# 08-I225-1.net
KiCad netlist of a schematic drawn in Altium Designer
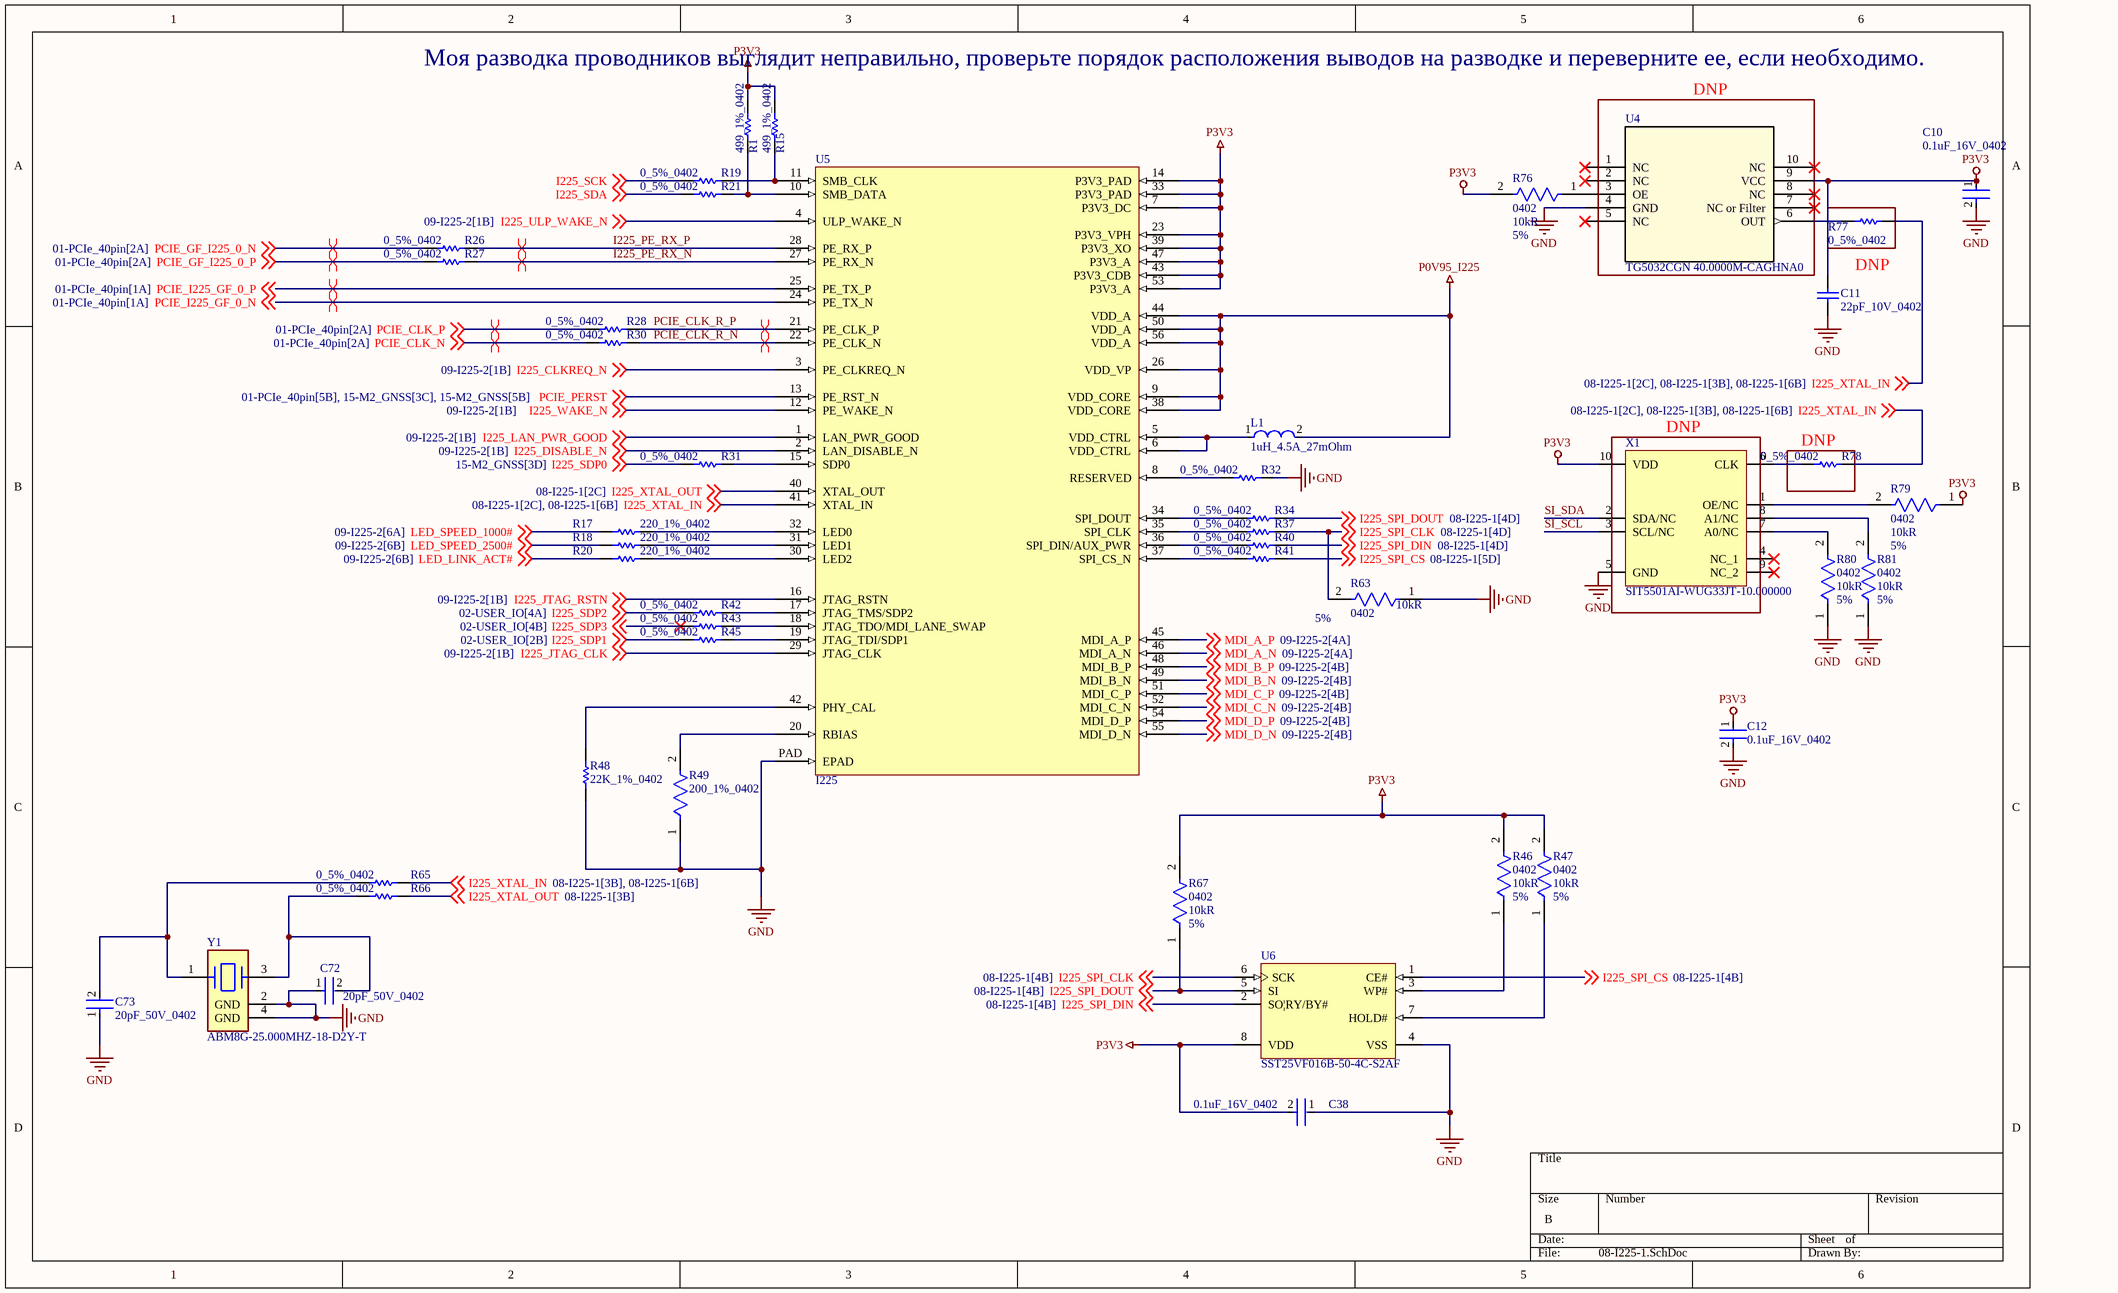
[diagram p0: 08-I225-1.SchDoc]

(export (version "E")
  (design (tool "Eeschema 10.0.6"))
  (components
    (comp (ref "C10")
      (value "0.1uF_16V_0402")
      (footprint "FP-GRM15-MFG")
      (description "CAP CER 0.1UF 16V X7R 0402")
      (fields (field (name "MANUFACTURER PART NUMBER") "GRM155R71C104KA88D") (field (name "TOLERANCE") "10%"))
      (libsource (lib "Altium Content Vault") (part "236180d848d6139a670b325ea6854c9"))
    )
    (comp (ref "C11")
      (value "22pF_10V_0402")
      (footprint "CAPC1005X56X25LL10T15")
      (fields
        (field (name "PART NUMBER") "0402ZA220JAT2A")
        (field (name "MANUFACTURER") "AVX Interconnect / Elco")
      )
      (libsource (lib "Altium Content Vault") (part "CAP"))
    )
    (comp (ref "C12")
      (value "0.1uF_16V_0402")
      (footprint "FP-GRM15-MFG")
      (description "CAP CER 0.1UF 16V X7R 0402")
      (fields (field (name "MANUFACTURER PART NUMBER") "GRM155R71C104KA88D") (field (name "TOLERANCE") "10%"))
      (libsource (lib "Altium Content Vault") (part "236180d848d6139a670b325ea6854c9"))
    )
    (comp (ref "C38")
      (value "0.1uF_16V_0402")
      (footprint "FP-GRM15-MFG")
      (description "CAP CER 0.1UF 16V X7R 0402")
      (fields (field (name "MANUFACTURER PART NUMBER") "GRM155R71C104KA88D") (field (name "TOLERANCE") "10%"))
      (libsource (lib "Altium Content Vault") (part "236180d848d6139a670b325ea6854c9"))
    )
    (comp (ref "C72")
      (value "20pF_50V_0402")
      (footprint "FP-C0402-BB-MFG")
      (description "CAP CER 20PF 50V 5% NP0 0402")
      (fields
        (field (name "MANUFACTURER PART NUMBER") "C0402C200J5GACTU")
        (field (name "OCTOPART") "https://octopart.com/c0402c200j5gactu-kemet-9143900")
      )
      (libsource (lib "Altium Content Vault") (part "b4654b650e69147ec39a6b967a45e02"))
    )
    (comp (ref "C73")
      (value "20pF_50V_0402")
      (footprint "FP-C0402-BB-MFG")
      (description "CAP CER 20PF 50V 5% NP0 0402")
      (fields
        (field (name "MANUFACTURER PART NUMBER") "C0402C200J5GACTU")
        (field (name "OCTOPART") "https://octopart.com/c0402c200j5gactu-kemet-9143900")
      )
      (libsource (lib "Altium Content Vault") (part "b4654b650e69147ec39a6b967a45e02"))
    )
    (comp (ref "L1")
      (value "1uH_4.5A_27mOhm")
      (footprint "FP-IHLP-1616BZ-FP_1_8545x-MFG")
      (description "Fixed Inductors Commercial Low DCR Series SMT 1uH 4.5A 27mΩ 20%")
      (fields (field (name "TOLERANCE") "20%"))
      (libsource (lib "Altium Content Vault") (part "725321dda6339637d4d059423bc1c3c"))
    )
    (comp (ref "R1")
      (value "499_1%_0402")
      (footprint "RESC1005X40X25LL05T05")
      (fields (field (name "MANUFACTURER") "Panasonic") (field (name "PART NUMBER") "ERJ-2RKF4990X"))
      (libsource (lib "Altium Content Vault") (part "RES"))
    )
    (comp (ref "R15")
      (value "499_1%_0402")
      (footprint "RESC1005X40X25LL05T05")
      (fields (field (name "MANUFACTURER") "Panasonic") (field (name "PART NUMBER") "ERJ-2RKF4990X"))
      (libsource (lib "Altium Content Vault") (part "RES"))
    )
    (comp (ref "R17")
      (value "220_1%_0402")
      (footprint "RESC1005X40X25NL10T10")
      (fields (field (name "PART NUMBER") "MC00625W04021220R") (field (name "MANUFACTURER") "Multicomp"))
      (libsource (lib "Altium Content Vault") (part "RES"))
    )
    (comp (ref "R18")
      (value "220_1%_0402")
      (footprint "RESC1005X40X25NL10T10")
      (fields (field (name "PART NUMBER") "MC00625W04021220R") (field (name "MANUFACTURER") "Multicomp"))
      (libsource (lib "Altium Content Vault") (part "RES"))
    )
    (comp (ref "R19")
      (value "0_5%_0402")
      (footprint "RESC1005X40X25LL10T10")
      (fields (field (name "MANUFACTURER") "KOA Speer") (field (name "PART NUMBER") "RK73Z1ETTP"))
      (libsource (lib "Altium Content Vault") (part "RES"))
    )
    (comp (ref "R20")
      (value "220_1%_0402")
      (footprint "RESC1005X40X25NL10T10")
      (fields (field (name "PART NUMBER") "MC00625W04021220R") (field (name "MANUFACTURER") "Multicomp"))
      (libsource (lib "Altium Content Vault") (part "RES"))
    )
    (comp (ref "R21")
      (value "0_5%_0402")
      (footprint "RESC1005X40X25LL10T10")
      (fields (field (name "MANUFACTURER") "KOA Speer") (field (name "PART NUMBER") "RK73Z1ETTP"))
      (libsource (lib "Altium Content Vault") (part "RES"))
    )
    (comp (ref "R26")
      (value "0_5%_0402")
      (footprint "RESC1005X40X25LL10T10")
      (fields (field (name "MANUFACTURER") "KOA Speer") (field (name "PART NUMBER") "RK73Z1ETTP"))
      (libsource (lib "Altium Content Vault") (part "RES"))
    )
    (comp (ref "R27")
      (value "0_5%_0402")
      (footprint "RESC1005X40X25LL10T10")
      (fields (field (name "MANUFACTURER") "KOA Speer") (field (name "PART NUMBER") "RK73Z1ETTP"))
      (libsource (lib "Altium Content Vault") (part "RES"))
    )
    (comp (ref "R28")
      (value "0_5%_0402")
      (footprint "RESC1005X40X25LL10T10")
      (fields (field (name "MANUFACTURER") "KOA Speer") (field (name "PART NUMBER") "RK73Z1ETTP"))
      (libsource (lib "Altium Content Vault") (part "RES"))
    )
    (comp (ref "R30")
      (value "0_5%_0402")
      (footprint "RESC1005X40X25LL10T10")
      (fields (field (name "MANUFACTURER") "KOA Speer") (field (name "PART NUMBER") "RK73Z1ETTP"))
      (libsource (lib "Altium Content Vault") (part "RES"))
    )
    (comp (ref "R31")
      (value "0_5%_0402")
      (footprint "RESC1005X40X25LL10T10")
      (fields (field (name "MANUFACTURER") "KOA Speer") (field (name "PART NUMBER") "RK73Z1ETTP"))
      (libsource (lib "Altium Content Vault") (part "RES"))
    )
    (comp (ref "R32")
      (value "0_5%_0402")
      (footprint "RESC1005X40X25LL10T10")
      (fields (field (name "MANUFACTURER") "KOA Speer") (field (name "PART NUMBER") "RK73Z1ETTP"))
      (libsource (lib "Altium Content Vault") (part "RES"))
    )
    (comp (ref "R34")
      (value "0_5%_0402")
      (footprint "RESC1005X40X25LL10T10")
      (fields (field (name "MANUFACTURER") "KOA Speer") (field (name "PART NUMBER") "RK73Z1ETTP"))
      (libsource (lib "Altium Content Vault") (part "RES"))
    )
    (comp (ref "R37")
      (value "0_5%_0402")
      (footprint "RESC1005X40X25LL10T10")
      (fields (field (name "MANUFACTURER") "KOA Speer") (field (name "PART NUMBER") "RK73Z1ETTP"))
      (libsource (lib "Altium Content Vault") (part "RES"))
    )
    (comp (ref "R40")
      (value "0_5%_0402")
      (footprint "RESC1005X40X25LL10T10")
      (fields (field (name "MANUFACTURER") "KOA Speer") (field (name "PART NUMBER") "RK73Z1ETTP"))
      (libsource (lib "Altium Content Vault") (part "RES"))
    )
    (comp (ref "R41")
      (value "0_5%_0402")
      (footprint "RESC1005X40X25LL10T10")
      (fields (field (name "MANUFACTURER") "KOA Speer") (field (name "PART NUMBER") "RK73Z1ETTP"))
      (libsource (lib "Altium Content Vault") (part "RES"))
    )
    (comp (ref "R42")
      (value "0_5%_0402")
      (footprint "RESC1005X40X25LL10T10")
      (fields (field (name "MANUFACTURER") "KOA Speer") (field (name "PART NUMBER") "RK73Z1ETTP"))
      (libsource (lib "Altium Content Vault") (part "RES"))
    )
    (comp (ref "R43")
      (value "0_5%_0402")
      (footprint "RESC1005X40X25LL10T10")
      (fields (field (name "MANUFACTURER") "KOA Speer") (field (name "PART NUMBER") "RK73Z1ETTP"))
      (libsource (lib "Altium Content Vault") (part "RES"))
    )
    (comp (ref "R45")
      (value "0_5%_0402")
      (footprint "RESC1005X40X25LL10T10")
      (fields (field (name "MANUFACTURER") "KOA Speer") (field (name "PART NUMBER") "RK73Z1ETTP"))
      (libsource (lib "Altium Content Vault") (part "RES"))
    )
    (comp (ref "R46")
      (value "CRCW040210K0JNED")
      (footprint "FP-CRCW0402-e3-IPC_B")
      (description "RES Thick Film, 10kΩ, 5%, 0.063W, 200ppm/°C, 0402")
      (fields
        (field (name "CASE/PACKAGE") "0402")
        (field (name "RESISTANCE") "10kR")
        (field (name "TOLERANCE") "5%")
      )
      (libsource (lib "Altium Content Vault") (part "1029c3af85768c4190bb7ad29bc67b5"))
    )
    (comp (ref "R47")
      (value "CRCW040210K0JNED")
      (footprint "FP-CRCW0402-e3-IPC_B")
      (description "RES Thick Film, 10kΩ, 5%, 0.063W, 200ppm/°C, 0402")
      (fields
        (field (name "CASE/PACKAGE") "0402")
        (field (name "RESISTANCE") "10kR")
        (field (name "TOLERANCE") "5%")
      )
      (libsource (lib "Altium Content Vault") (part "1029c3af85768c4190bb7ad29bc67b5"))
    )
    (comp (ref "R48")
      (value "22K_1%_0402")
      (footprint "RESC1005X40X25NL05T05")
      (fields (field (name "PART NUMBER") "CRCW040222K0FKED") (field (name "MANUFACTURER") "Vishay Dale"))
      (libsource (lib "Altium Content Vault") (part "RES"))
    )
    (comp (ref "R49")
      (value "200_1%_0402")
      (footprint "FP-CRCW0402-e3-IPC_C")
      (description "RES Thick Film, 200Ω, 1%, 0.063W, 100ppm/°C, 0402")
      (fields (field (name "TOLERANCE") "1%"))
      (libsource (lib "Altium Content Vault") (part "1029c3af85768c4190bb7ad29bc67b5"))
    )
    (comp (ref "R63")
      (value "CRCW040210K0JNED")
      (footprint "FP-CRCW0402-e3-IPC_B")
      (description "RES Thick Film, 10kΩ, 5%, 0.063W, 200ppm/°C, 0402")
      (fields
        (field (name "CASE/PACKAGE") "0402")
        (field (name "RESISTANCE") "10kR")
        (field (name "TOLERANCE") "5%")
      )
      (libsource (lib "Altium Content Vault") (part "1029c3af85768c4190bb7ad29bc67b5"))
    )
    (comp (ref "R65")
      (value "0_5%_0402")
      (footprint "RESC1005X40X25LL10T10")
      (fields (field (name "MANUFACTURER") "KOA Speer") (field (name "PART NUMBER") "RK73Z1ETTP"))
      (libsource (lib "Altium Content Vault") (part "RES"))
    )
    (comp (ref "R66")
      (value "0_5%_0402")
      (footprint "RESC1005X40X25LL10T10")
      (fields (field (name "MANUFACTURER") "KOA Speer") (field (name "PART NUMBER") "RK73Z1ETTP"))
      (libsource (lib "Altium Content Vault") (part "RES"))
    )
    (comp (ref "R67")
      (value "CRCW040210K0JNED")
      (footprint "FP-CRCW0402-e3-IPC_B")
      (description "RES Thick Film, 10kΩ, 5%, 0.063W, 200ppm/°C, 0402")
      (fields
        (field (name "CASE/PACKAGE") "0402")
        (field (name "RESISTANCE") "10kR")
        (field (name "TOLERANCE") "5%")
      )
      (libsource (lib "Altium Content Vault") (part "1029c3af85768c4190bb7ad29bc67b5"))
    )
    (comp (ref "R76")
      (value "CRCW040210K0JNED")
      (footprint "FP-CRCW0402-e3-IPC_B")
      (description "RES Thick Film, 10kΩ, 5%, 0.063W, 200ppm/°C, 0402")
      (fields
        (field (name "CASE/PACKAGE") "0402")
        (field (name "RESISTANCE") "10kR")
        (field (name "TOLERANCE") "5%")
      )
      (libsource (lib "Altium Content Vault") (part "1029c3af85768c4190bb7ad29bc67b5"))
    )
    (comp (ref "R77")
      (value "0_5%_0402")
      (footprint "RESC1005X40X25LL10T10")
      (fields (field (name "MANUFACTURER") "KOA Speer") (field (name "PART NUMBER") "RK73Z1ETTP"))
      (libsource (lib "Altium Content Vault") (part "RES"))
    )
    (comp (ref "R78")
      (value "0_5%_0402")
      (footprint "RESC1005X40X25LL10T10")
      (fields (field (name "MANUFACTURER") "KOA Speer") (field (name "PART NUMBER") "RK73Z1ETTP"))
      (libsource (lib "Altium Content Vault") (part "RES"))
    )
    (comp (ref "R79")
      (value "CRCW040210K0JNED")
      (footprint "FP-CRCW0402-e3-IPC_B")
      (description "RES Thick Film, 10kΩ, 5%, 0.063W, 200ppm/°C, 0402")
      (fields
        (field (name "CASE/PACKAGE") "0402")
        (field (name "RESISTANCE") "10kR")
        (field (name "TOLERANCE") "5%")
      )
      (libsource (lib "Altium Content Vault") (part "1029c3af85768c4190bb7ad29bc67b5"))
    )
    (comp (ref "R80")
      (value "CRCW040210K0JNED")
      (footprint "FP-CRCW0402-e3-IPC_B")
      (description "RES Thick Film, 10kΩ, 5%, 0.063W, 200ppm/°C, 0402")
      (fields
        (field (name "CASE/PACKAGE") "0402")
        (field (name "RESISTANCE") "10kR")
        (field (name "TOLERANCE") "5%")
      )
      (libsource (lib "Altium Content Vault") (part "1029c3af85768c4190bb7ad29bc67b5"))
    )
    (comp (ref "R81")
      (value "CRCW040210K0JNED")
      (footprint "FP-CRCW0402-e3-IPC_B")
      (description "RES Thick Film, 10kΩ, 5%, 0.063W, 200ppm/°C, 0402")
      (fields
        (field (name "CASE/PACKAGE") "0402")
        (field (name "RESISTANCE") "10kR")
        (field (name "TOLERANCE") "5%")
      )
      (libsource (lib "Altium Content Vault") (part "1029c3af85768c4190bb7ad29bc67b5"))
    )
    (comp (ref "U4")
      (value "TG5032CGN 40.0000M-CAGHNA0")
      (footprint "QFN10_TG5032CGN 40.0000M-CAGHNA0_EPS")
      (description "No Description Available")
      (fields (field (name "COPYRIGHT") "Copyright (C) 2024 Ultra Librarian. All rights reserved."))
      (libsource (lib "TG5032CGN40P0000M-CAGHNA0") (part "TG5032CGN 40.0000M-CAGHNA0"))
    )
    (comp (ref "U5") (value "I225") (footprint "I225 QFN56") (libsource (lib "TimeStick_Lib") (part "I225")))
    (comp (ref "U6")
      (value "SST25VF016B-50-4C-S2AF")
      (footprint "MCHP-SOIC-S2A8_M")
      (description "16 Mbit SPI Serial Flash, 2.7 to 3.6 V, 50 MHz, 0 to 70 degC, 8-pin SOIC (S2A8), Tube")
      (fields (field (name "MANUFACTURER") "Microchip"))
      (libsource (lib "Altium Content Vault") (part "MCHP-SST25VFXXXB-SOIX-8"))
    )
    (comp (ref "X1")
      (value "SIT5501AI-WUG33JT-10.000000")
      (footprint "XTAL_SiT5501_70x50")
      (description "1 MHz  60 MHz, Elite X Stratum 3E Precision Oscillator")
      (libsource (lib "LotusSound") (part "XTAL_SIT5501AI-WUG33JT-10.000000"))
    )
    (comp (ref "Y1")
      (value "ABM8G-25.000MHZ-18-D2Y-T")
      (footprint "FP-ABM8G-MFG")
      (description "CRYSTAL 25.0000MHZ 18PF SMD")
      (fields
        (field (name "MANUFACTURER") "Abracon")
        (field (name "OCTOPART") "https://octopart.com/abm8g-25.000mhz-18-d2y-t-abracon-12676602")
      )
      (libsource (lib "Altium Content Vault") (part "82af6c543cb7a88a4cbd02a3a01c293"))
    )
  )
  (nets
    (net (code "1") (name "/I225_PE_RX_N") (class "Default")
      (node (ref "R27") (pin "2") (pinfunction "2_2") (pintype "passive"))
      (node (ref "U5") (pin "27") (pinfunction "PE_RX_N_27") (pintype "input"))
    )
    (net (code "2") (name "/I225_PE_RX_P") (class "Default")
      (node (ref "R26") (pin "2") (pinfunction "2_2") (pintype "passive"))
      (node (ref "U5") (pin "28") (pinfunction "PE_RX_P_28") (pintype "input"))
    )
    (net (code "3") (name "/PCIE_CLK_R_N") (class "Default")
      (node (ref "R30") (pin "2") (pinfunction "2_2") (pintype "passive"))
      (node (ref "U5") (pin "22") (pinfunction "PE_CLK_N_22") (pintype "input"))
    )
    (net (code "4") (name "/PCIE_CLK_R_P") (class "Default")
      (node (ref "R28") (pin "2") (pinfunction "2_2") (pintype "passive"))
      (node (ref "U5") (pin "21") (pinfunction "PE_CLK_P_21") (pintype "input"))
    )
    (net (code "5") (name "/SI_SCL") (class "Default")
      (node (ref "X1") (pin "3") (pinfunction "SCL/NC_3") (pintype "passive"))
    )
    (net (code "6") (name "/SI_SDA") (class "Default")
      (node (ref "X1") (pin "2") (pinfunction "SDA/NC_2") (pintype "passive"))
    )
    (net (code "7") (name "GND") (class "Default")
      (node (ref "C10") (pin "2") (pinfunction "2_2") (pintype "passive"))
      (node (ref "C11") (pin "1") (pinfunction "1_1") (pintype "passive"))
      (node (ref "C12") (pin "2") (pinfunction "2_2") (pintype "passive"))
      (node (ref "C38") (pin "1") (pinfunction "1_1") (pintype "passive"))
      (node (ref "C72") (pin "1") (pinfunction "1_1") (pintype "passive"))
      (node (ref "C73") (pin "1") (pinfunction "1_1") (pintype "passive"))
      (node (ref "R32") (pin "2") (pinfunction "2_2") (pintype "passive"))
      (node (ref "R48") (pin "1") (pinfunction "1_1") (pintype "passive"))
      (node (ref "R49") (pin "1") (pinfunction "1_1") (pintype "passive"))
      (node (ref "R63") (pin "1") (pinfunction "1_1") (pintype "passive"))
      (node (ref "R80") (pin "1") (pinfunction "1_1") (pintype "passive"))
      (node (ref "R81") (pin "1") (pinfunction "1_1") (pintype "passive"))
      (node (ref "U4") (pin "4") (pinfunction "GND_4") (pintype "power_in"))
      (node (ref "U5") (pin "PAD") (pinfunction "EPAD_PAD") (pintype "input"))
      (node (ref "U6") (pin "4") (pinfunction "VSS_4") (pintype "power_in"))
      (node (ref "X1") (pin "5") (pinfunction "GND_5") (pintype "passive"))
      (node (ref "Y1") (pin "2") (pinfunction "GND_2") (pintype "power_in"))
      (node (ref "Y1") (pin "4") (pinfunction "GND_4") (pintype "power_in"))
    )
    (net (code "8") (name "I225_CLKREQ_N") (class "Default")
      (node (ref "U5") (pin "3") (pinfunction "PE_CLKREQ_N_3") (pintype "input"))
    )
    (net (code "9") (name "I225_DISABLE_N") (class "Default")
      (node (ref "U5") (pin "2") (pinfunction "LAN_DISABLE_N_2") (pintype "input"))
    )
    (net (code "10") (name "I225_JTAG_CLK") (class "Default")
      (node (ref "U5") (pin "29") (pinfunction "JTAG_CLK_29") (pintype "input"))
    )
    (net (code "11") (name "I225_JTAG_RSTN") (class "Default")
      (node (ref "U5") (pin "16") (pinfunction "JTAG_RSTN_16") (pintype "input"))
    )
    (net (code "12") (name "I225_LAN_PWR_GOOD") (class "Default")
      (node (ref "U5") (pin "1") (pinfunction "LAN_PWR_GOOD_1") (pintype "input"))
    )
    (net (code "13") (name "I225_SCK") (class "Default")
      (node (ref "R19") (pin "1") (pinfunction "1_1") (pintype "passive"))
    )
    (net (code "14") (name "I225_SDA") (class "Default")
      (node (ref "R21") (pin "1") (pinfunction "1_1") (pintype "passive"))
    )
    (net (code "15") (name "I225_SDP0") (class "Default")
      (node (ref "R31") (pin "1") (pinfunction "1_1") (pintype "passive"))
    )
    (net (code "16") (name "I225_SDP1") (class "Default")
      (node (ref "R45") (pin "1") (pinfunction "1_1") (pintype "passive"))
    )
    (net (code "17") (name "I225_SDP2") (class "Default")
      (node (ref "R42") (pin "1") (pinfunction "1_1") (pintype "passive"))
    )
    (net (code "18") (name "I225_SDP3") (class "Default")
      (node (ref "R43") (pin "1") (pinfunction "1_1") (pintype "passive"))
    )
    (net (code "19") (name "I225_SPI_CLK") (class "Default")
      (node (ref "R37") (pin "2") (pinfunction "2_2") (pintype "passive"))
      (node (ref "R63") (pin "2") (pinfunction "2_2") (pintype "passive"))
      (node (ref "U6") (pin "6") (pinfunction "SCK_6") (pintype "input"))
    )
    (net (code "20") (name "I225_SPI_CS") (class "Default")
      (node (ref "R41") (pin "2") (pinfunction "2_2") (pintype "passive"))
      (node (ref "U6") (pin "1") (pinfunction "CE#_1") (pintype "input"))
    )
    (net (code "21") (name "I225_SPI_DIN") (class "Default")
      (node (ref "R40") (pin "2") (pinfunction "2_2") (pintype "passive"))
      (node (ref "U6") (pin "2") (pinfunction "SO¦RY/BY#_2") (pintype "tri_state"))
    )
    (net (code "22") (name "I225_SPI_DOUT") (class "Default")
      (node (ref "R34") (pin "2") (pinfunction "2_2") (pintype "passive"))
      (node (ref "R67") (pin "1") (pinfunction "1_1") (pintype "passive"))
      (node (ref "U6") (pin "5") (pinfunction "SI_5") (pintype "input"))
    )
    (net (code "23") (name "I225_ULP_WAKE_N") (class "Default")
      (node (ref "U5") (pin "4") (pinfunction "ULP_WAKE_N_4") (pintype "input"))
    )
    (net (code "24") (name "I225_WAKE_N") (class "Default")
      (node (ref "U5") (pin "12") (pinfunction "PE_WAKE_N_12") (pintype "input"))
    )
    (net (code "25") (name "I225_XTAL_IN") (class "Default")
      (node (ref "R65") (pin "2") (pinfunction "2_2") (pintype "passive"))
      (node (ref "R77") (pin "2") (pinfunction "2_2") (pintype "passive"))
      (node (ref "R78") (pin "2") (pinfunction "2_2") (pintype "passive"))
      (node (ref "U5") (pin "41") (pinfunction "XTAL_IN_41") (pintype "input"))
    )
    (net (code "26") (name "I225_XTAL_OUT") (class "Default")
      (node (ref "R66") (pin "2") (pinfunction "2_2") (pintype "passive"))
      (node (ref "U5") (pin "40") (pinfunction "XTAL_OUT_40") (pintype "input"))
    )
    (net (code "27") (name "LED_LINK_ACT#") (class "Default")
      (node (ref "R20") (pin "1") (pinfunction "1_1") (pintype "passive"))
    )
    (net (code "28") (name "LED_SPEED_1000#") (class "Default")
      (node (ref "R17") (pin "1") (pinfunction "1_1") (pintype "passive"))
    )
    (net (code "29") (name "LED_SPEED_2500#") (class "Default")
      (node (ref "R18") (pin "1") (pinfunction "1_1") (pintype "passive"))
    )
    (net (code "30") (name "MDI_A_N") (class "Default")
      (node (ref "U5") (pin "46") (pinfunction "MDI_A_N_46") (pintype "input"))
    )
    (net (code "31") (name "MDI_A_P") (class "Default")
      (node (ref "U5") (pin "45") (pinfunction "MDI_A_P_45") (pintype "input"))
    )
    (net (code "32") (name "MDI_B_N") (class "Default")
      (node (ref "U5") (pin "49") (pinfunction "MDI_B_N_49") (pintype "input"))
    )
    (net (code "33") (name "MDI_B_P") (class "Default")
      (node (ref "U5") (pin "48") (pinfunction "MDI_B_P_48") (pintype "input"))
    )
    (net (code "34") (name "MDI_C_N") (class "Default")
      (node (ref "U5") (pin "52") (pinfunction "MDI_C_N_52") (pintype "input"))
    )
    (net (code "35") (name "MDI_C_P") (class "Default")
      (node (ref "U5") (pin "51") (pinfunction "MDI_C_P_51") (pintype "input"))
    )
    (net (code "36") (name "MDI_D_N") (class "Default")
      (node (ref "U5") (pin "55") (pinfunction "MDI_D_N_55") (pintype "input"))
    )
    (net (code "37") (name "MDI_D_P") (class "Default")
      (node (ref "U5") (pin "54") (pinfunction "MDI_D_P_54") (pintype "input"))
    )
    (net (code "38") (name "Net-(C72-Pad2)") (class "Default")
      (node (ref "C72") (pin "2") (pinfunction "2_2") (pintype "passive"))
      (node (ref "R66") (pin "1") (pinfunction "1_1") (pintype "passive"))
      (node (ref "Y1") (pin "3") (pinfunction "3_3") (pintype "passive"))
    )
    (net (code "39") (name "Net-(C73-Pad2)") (class "Default")
      (node (ref "C73") (pin "2") (pinfunction "2_2") (pintype "passive"))
      (node (ref "R65") (pin "1") (pinfunction "1_1") (pintype "passive"))
      (node (ref "Y1") (pin "1") (pinfunction "1_1") (pintype "passive"))
    )
    (net (code "40") (name "Net-(L1-Pad1)") (class "Default")
      (node (ref "L1") (pin "1") (pinfunction "1_1") (pintype "passive"))
      (node (ref "U5") (pin "5") (pinfunction "VDD_CTRL_5") (pintype "input"))
      (node (ref "U5") (pin "6") (pinfunction "VDD_CTRL_6") (pintype "input"))
    )
    (net (code "41") (name "Net-(U4-OE)") (class "Default")
      (node (ref "R76") (pin "1") (pinfunction "1_1") (pintype "passive"))
      (node (ref "U4") (pin "3") (pinfunction "OE_3") (pintype "passive"))
    )
    (net (code "42") (name "Net-(U4-OUT)") (class "Default")
      (node (ref "R77") (pin "1") (pinfunction "1_1") (pintype "passive"))
      (node (ref "U4") (pin "6") (pinfunction "OUT_6") (pintype "output"))
    )
    (net (code "43") (name "Net-(U5-JTAG_TDI{slash}SDP1)") (class "Default")
      (node (ref "R45") (pin "2") (pinfunction "2_2") (pintype "passive"))
      (node (ref "U5") (pin "19") (pinfunction "JTAG_TDI/SDP1_19") (pintype "input"))
    )
    (net (code "44") (name "Net-(U5-JTAG_TDO{slash}MDI_LANE_SWAP)") (class "Default")
      (node (ref "R43") (pin "2") (pinfunction "2_2") (pintype "passive"))
      (node (ref "U5") (pin "18") (pinfunction "JTAG_TDO/MDI_LANE_SWAP_18") (pintype "input"))
    )
    (net (code "45") (name "Net-(U5-JTAG_TMS{slash}SDP2)") (class "Default")
      (node (ref "R42") (pin "2") (pinfunction "2_2") (pintype "passive"))
      (node (ref "U5") (pin "17") (pinfunction "JTAG_TMS/SDP2_17") (pintype "input"))
    )
    (net (code "46") (name "Net-(U5-LED0)") (class "Default")
      (node (ref "R17") (pin "2") (pinfunction "2_2") (pintype "passive"))
      (node (ref "U5") (pin "32") (pinfunction "LED0_32") (pintype "input"))
    )
    (net (code "47") (name "Net-(U5-LED1)") (class "Default")
      (node (ref "R18") (pin "2") (pinfunction "2_2") (pintype "passive"))
      (node (ref "U5") (pin "31") (pinfunction "LED1_31") (pintype "input"))
    )
    (net (code "48") (name "Net-(U5-LED2)") (class "Default")
      (node (ref "R20") (pin "2") (pinfunction "2_2") (pintype "passive"))
      (node (ref "U5") (pin "30") (pinfunction "LED2_30") (pintype "input"))
    )
    (net (code "49") (name "Net-(U5-PHY_CAL)") (class "Default")
      (node (ref "R48") (pin "2") (pinfunction "2_2") (pintype "passive"))
      (node (ref "U5") (pin "42") (pinfunction "PHY_CAL_42") (pintype "input"))
    )
    (net (code "50") (name "Net-(U5-RBIAS)") (class "Default")
      (node (ref "R49") (pin "2") (pinfunction "2_2") (pintype "passive"))
      (node (ref "U5") (pin "20") (pinfunction "RBIAS_20") (pintype "input"))
    )
    (net (code "51") (name "Net-(U5-RESERVED)") (class "Default")
      (node (ref "R32") (pin "1") (pinfunction "1_1") (pintype "passive"))
      (node (ref "U5") (pin "8") (pinfunction "RESERVED_8") (pintype "input"))
    )
    (net (code "52") (name "Net-(U5-SDP0)") (class "Default")
      (node (ref "R31") (pin "2") (pinfunction "2_2") (pintype "passive"))
      (node (ref "U5") (pin "15") (pinfunction "SDP0_15") (pintype "input"))
    )
    (net (code "53") (name "Net-(U5-SMB_CLK)") (class "Default")
      (node (ref "R15") (pin "1") (pinfunction "1_1") (pintype "passive"))
      (node (ref "R19") (pin "2") (pinfunction "2_2") (pintype "passive"))
      (node (ref "U5") (pin "11") (pinfunction "SMB_CLK_11") (pintype "input"))
    )
    (net (code "54") (name "Net-(U5-SMB_DATA)") (class "Default")
      (node (ref "R1") (pin "1") (pinfunction "1_1") (pintype "passive"))
      (node (ref "R21") (pin "2") (pinfunction "2_2") (pintype "passive"))
      (node (ref "U5") (pin "10") (pinfunction "SMB_DATA_10") (pintype "input"))
    )
    (net (code "55") (name "Net-(U5-SPI_CLK)") (class "Default")
      (node (ref "R37") (pin "1") (pinfunction "1_1") (pintype "passive"))
      (node (ref "U5") (pin "35") (pinfunction "SPI_CLK_35") (pintype "input"))
    )
    (net (code "56") (name "Net-(U5-SPI_CS_N)") (class "Default")
      (node (ref "R41") (pin "1") (pinfunction "1_1") (pintype "passive"))
      (node (ref "U5") (pin "37") (pinfunction "SPI_CS_N_37") (pintype "input"))
    )
    (net (code "57") (name "Net-(U5-SPI_DIN{slash}AUX_PWR)") (class "Default")
      (node (ref "R40") (pin "1") (pinfunction "1_1") (pintype "passive"))
      (node (ref "U5") (pin "36") (pinfunction "SPI_DIN/AUX_PWR_36") (pintype "input"))
    )
    (net (code "58") (name "Net-(U5-SPI_DOUT)") (class "Default")
      (node (ref "R34") (pin "1") (pinfunction "1_1") (pintype "passive"))
      (node (ref "U5") (pin "34") (pinfunction "SPI_DOUT_34") (pintype "input"))
    )
    (net (code "59") (name "Net-(U6-HOLD#)") (class "Default")
      (node (ref "R47") (pin "1") (pinfunction "1_1") (pintype "passive"))
      (node (ref "U6") (pin "7") (pinfunction "HOLD#_7") (pintype "input"))
    )
    (net (code "60") (name "Net-(U6-WP#)") (class "Default")
      (node (ref "R46") (pin "1") (pinfunction "1_1") (pintype "passive"))
      (node (ref "U6") (pin "3") (pinfunction "WP#_3") (pintype "input"))
    )
    (net (code "61") (name "Net-(X1-A0{slash}NC)") (class "Default")
      (node (ref "R80") (pin "2") (pinfunction "2_2") (pintype "passive"))
      (node (ref "X1") (pin "7") (pinfunction "A0/NC_7") (pintype "passive"))
    )
    (net (code "62") (name "Net-(X1-A1{slash}NC)") (class "Default")
      (node (ref "R81") (pin "2") (pinfunction "2_2") (pintype "passive"))
      (node (ref "X1") (pin "8") (pinfunction "A1/NC_8") (pintype "passive"))
    )
    (net (code "63") (name "Net-(X1-CLK)") (class "Default")
      (node (ref "R78") (pin "1") (pinfunction "1_1") (pintype "passive"))
      (node (ref "X1") (pin "6") (pinfunction "CLK_6") (pintype "passive"))
    )
    (net (code "64") (name "Net-(X1-OE{slash}NC)") (class "Default")
      (node (ref "R79") (pin "2") (pinfunction "2_2") (pintype "passive"))
      (node (ref "X1") (pin "1") (pinfunction "OE/NC_1") (pintype "passive"))
    )
    (net (code "65") (name "P0V95_I225") (class "Default")
      (node (ref "L1") (pin "2") (pinfunction "2_2") (pintype "passive"))
      (node (ref "U5") (pin "26") (pinfunction "VDD_VP_26") (pintype "input"))
      (node (ref "U5") (pin "38") (pinfunction "VDD_CORE_38") (pintype "input"))
      (node (ref "U5") (pin "44") (pinfunction "VDD_A_44") (pintype "input"))
      (node (ref "U5") (pin "50") (pinfunction "VDD_A_50") (pintype "input"))
      (node (ref "U5") (pin "56") (pinfunction "VDD_A_56") (pintype "input"))
      (node (ref "U5") (pin "9") (pinfunction "VDD_CORE_9") (pintype "input"))
    )
    (net (code "66") (name "P3V3") (class "Default")
      (node (ref "C10") (pin "1") (pinfunction "1_1") (pintype "passive"))
      (node (ref "C11") (pin "2") (pinfunction "2_2") (pintype "passive"))
      (node (ref "C12") (pin "1") (pinfunction "1_1") (pintype "passive"))
      (node (ref "C38") (pin "2") (pinfunction "2_2") (pintype "passive"))
      (node (ref "R1") (pin "2") (pinfunction "2_2") (pintype "passive"))
      (node (ref "R15") (pin "2") (pinfunction "2_2") (pintype "passive"))
      (node (ref "R46") (pin "2") (pinfunction "2_2") (pintype "passive"))
      (node (ref "R47") (pin "2") (pinfunction "2_2") (pintype "passive"))
      (node (ref "R67") (pin "2") (pinfunction "2_2") (pintype "passive"))
      (node (ref "R76") (pin "2") (pinfunction "2_2") (pintype "passive"))
      (node (ref "R79") (pin "1") (pinfunction "1_1") (pintype "passive"))
      (node (ref "U4") (pin "9") (pinfunction "VCC_9") (pintype "power_in"))
      (node (ref "U5") (pin "14") (pinfunction "P3V3_PAD_14") (pintype "input"))
      (node (ref "U5") (pin "23") (pinfunction "P3V3_VPH_23") (pintype "input"))
      (node (ref "U5") (pin "33") (pinfunction "P3V3_PAD_33") (pintype "input"))
      (node (ref "U5") (pin "39") (pinfunction "P3V3_XO_39") (pintype "input"))
      (node (ref "U5") (pin "43") (pinfunction "P3V3_CDB_43") (pintype "input"))
      (node (ref "U5") (pin "47") (pinfunction "P3V3_A_47") (pintype "input"))
      (node (ref "U5") (pin "53") (pinfunction "P3V3_A_53") (pintype "input"))
      (node (ref "U5") (pin "7") (pinfunction "P3V3_DC_7") (pintype "input"))
      (node (ref "U6") (pin "8") (pinfunction "VDD_8") (pintype "power_in"))
      (node (ref "X1") (pin "10") (pinfunction "VDD_10") (pintype "passive"))
    )
    (net (code "67") (name "PCIE_CLK_N") (class "Default")
      (node (ref "R30") (pin "1") (pinfunction "1_1") (pintype "passive"))
    )
    (net (code "68") (name "PCIE_CLK_P") (class "Default")
      (node (ref "R28") (pin "1") (pinfunction "1_1") (pintype "passive"))
    )
    (net (code "69") (name "PCIE_GF_I225_0_N") (class "Default")
      (node (ref "R26") (pin "1") (pinfunction "1_1") (pintype "passive"))
    )
    (net (code "70") (name "PCIE_GF_I225_0_P") (class "Default")
      (node (ref "R27") (pin "1") (pinfunction "1_1") (pintype "passive"))
    )
    (net (code "71") (name "PCIE_I225_GF_0_N") (class "Default")
      (node (ref "U5") (pin "24") (pinfunction "PE_TX_N_24") (pintype "input"))
    )
    (net (code "72") (name "PCIE_I225_GF_0_P") (class "Default")
      (node (ref "U5") (pin "25") (pinfunction "PE_TX_P_25") (pintype "input"))
    )
    (net (code "73") (name "PCIE_PERST") (class "Default")
      (node (ref "U5") (pin "13") (pinfunction "PE_RST_N_13") (pintype "input"))
    )
    (net (code "74") (name "unconnected-(U4-NC-Pad1)") (class "Default")
      (node (ref "U4") (pin "1") (pinfunction "NC_1") (pintype "passive+no_connect"))
    )
    (net (code "75") (name "unconnected-(U4-NC-Pad2)") (class "Default")
      (node (ref "U4") (pin "2") (pinfunction "NC_2") (pintype "passive+no_connect"))
    )
    (net (code "76") (name "unconnected-(U4-NC-Pad5)") (class "Default")
      (node (ref "U4") (pin "5") (pinfunction "NC_5") (pintype "passive+no_connect"))
    )
    (net (code "77") (name "unconnected-(U4-NC-Pad8)") (class "Default")
      (node (ref "U4") (pin "8") (pinfunction "NC_8") (pintype "passive+no_connect"))
    )
    (net (code "78") (name "unconnected-(U4-NC-Pad10)") (class "Default")
      (node (ref "U4") (pin "10") (pinfunction "NC_10") (pintype "passive+no_connect"))
    )
    (net (code "79") (name "unconnected-(U4-NC_or_Filter-Pad7)") (class "Default")
      (node (ref "U4") (pin "7") (pinfunction "NC_or_Filter_7") (pintype "passive+no_connect"))
    )
    (net (code "80") (name "unconnected-(X1-NC_1-Pad4)") (class "Default")
      (node (ref "X1") (pin "4") (pinfunction "NC_1_4") (pintype "passive+no_connect"))
    )
    (net (code "81") (name "unconnected-(X1-NC_2-Pad9)") (class "Default")
      (node (ref "X1") (pin "9") (pinfunction "NC_2_9") (pintype "passive+no_connect"))
    )
  )
)
